# current_measurement.net
KiCad netlist of a schematic drawn in Altium Designer
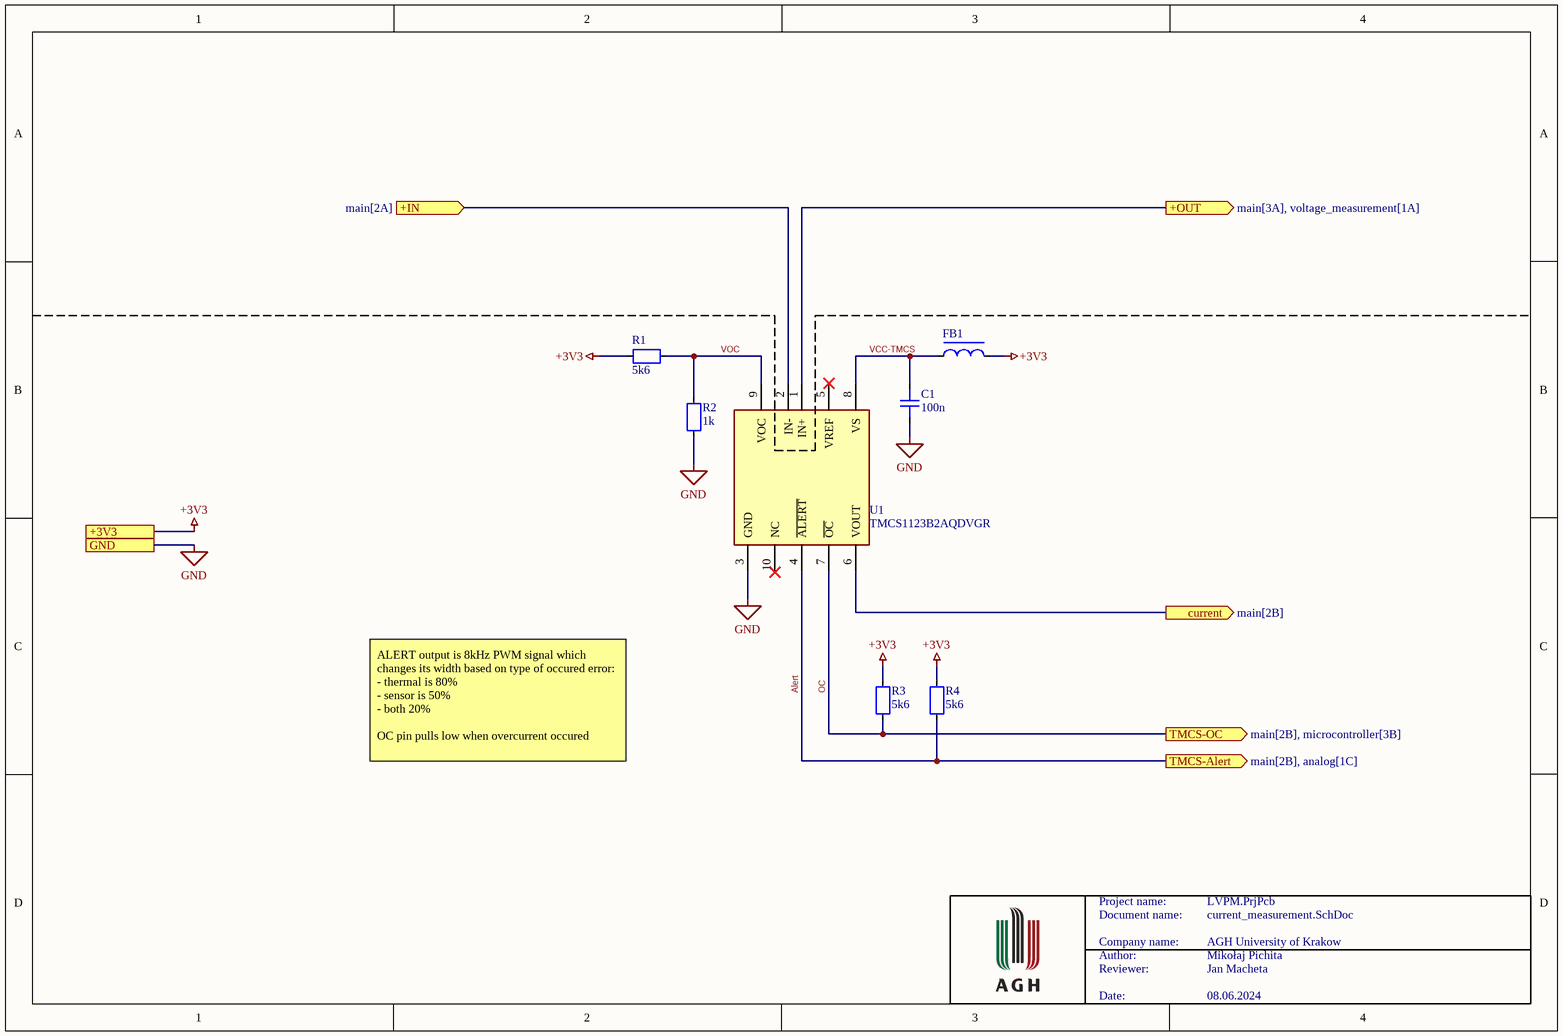
[diagram p0: current_measurement.SchDoc]

(export (version "E")
  (design (tool "Eeschema 10.0.6"))
  (components
    (comp (ref "C1")
      (value "100n")
      (footprint "CAP0603")
      (libsource (lib "Integrated_Library_main") (part "Capacitor"))
    )
    (comp (ref "FB1")
      (value "*")
      (footprint "FB0402")
      (libsource (lib "Integrated_Library_main") (part "Ferrite Bead"))
    )
    (comp (ref "R1")
      (value "5k6")
      (footprint "RES0603")
      (libsource (lib "Integrated_Library_main") (part "Resistor"))
    )
    (comp (ref "R2")
      (value "1k")
      (footprint "RES0603")
      (libsource (lib "Integrated_Library_main") (part "Resistor"))
    )
    (comp (ref "R3")
      (value "5k6")
      (footprint "RES0603")
      (libsource (lib "Integrated_Library_main") (part "Resistor"))
    )
    (comp (ref "R4")
      (value "5k6")
      (footprint "RES0603")
      (libsource (lib "Integrated_Library_main") (part "Resistor"))
    )
    (comp (ref "U1")
      (value "TMCS1123B2AQDVGR")
      (footprint "FP-DVG0010A-MFG")
      (libsource (lib "Integrated_Library_main") (part "TMCS1123B2AQDVGR"))
    )
  )
  (nets
    (net (code "1") (name "+3V3") (class "Default")
      (node (ref "FB1") (pin "2") (pintype "passive"))
      (node (ref "R1") (pin "2") (pintype "passive"))
      (node (ref "R3") (pin "1") (pintype "passive"))
      (node (ref "R4") (pin "1") (pintype "passive"))
    )
    (net (code "2") (name "/+IN") (class "Default")
      (node (ref "U1") (pin "2") (pinfunction "IN-_2") (pintype "passive"))
    )
    (net (code "3") (name "/+OUT") (class "Default")
      (node (ref "U1") (pin "1") (pinfunction "IN+_1") (pintype "passive"))
    )
    (net (code "4") (name "/Alert") (class "Default")
      (node (ref "R4") (pin "2") (pintype "passive"))
      (node (ref "U1") (pin "4") (pinfunction "~{ALERT}_4") (pintype "open_collector"))
    )
    (net (code "5") (name "/OC") (class "Default")
      (node (ref "R3") (pin "2") (pintype "passive"))
      (node (ref "U1") (pin "7") (pinfunction "~{OC}_7") (pintype "open_collector"))
    )
    (net (code "6") (name "/VCC-TMCS") (class "Default")
      (node (ref "C1") (pin "1") (pintype "passive"))
      (node (ref "FB1") (pin "1") (pintype "passive"))
      (node (ref "U1") (pin "8") (pinfunction "VS_8") (pintype "power_in"))
    )
    (net (code "7") (name "/VOC") (class "Default")
      (node (ref "R1") (pin "1") (pintype "passive"))
      (node (ref "R2") (pin "1") (pintype "passive"))
      (node (ref "U1") (pin "9") (pinfunction "VOC_9") (pintype "passive"))
    )
    (net (code "8") (name "/current") (class "Default")
      (node (ref "U1") (pin "6") (pinfunction "VOUT_6") (pintype "passive"))
    )
    (net (code "9") (name "GND") (class "Default")
      (node (ref "C1") (pin "2") (pintype "passive"))
      (node (ref "R2") (pin "2") (pintype "passive"))
      (node (ref "U1") (pin "3") (pinfunction "GND_3") (pintype "power_in"))
    )
    (net (code "10") (name "unconnected-(U1-NC-Pad10)") (class "Default")
      (node (ref "U1") (pin "10") (pinfunction "NC_10") (pintype "passive+no_connect"))
    )
    (net (code "11") (name "unconnected-(U1-VREF-Pad5)") (class "Default")
      (node (ref "U1") (pin "5") (pinfunction "VREF_5") (pintype "passive+no_connect"))
    )
  )
)
